# Alimentatore_LM317.net
KiCad netlist of a schematic drawn in EAGLE
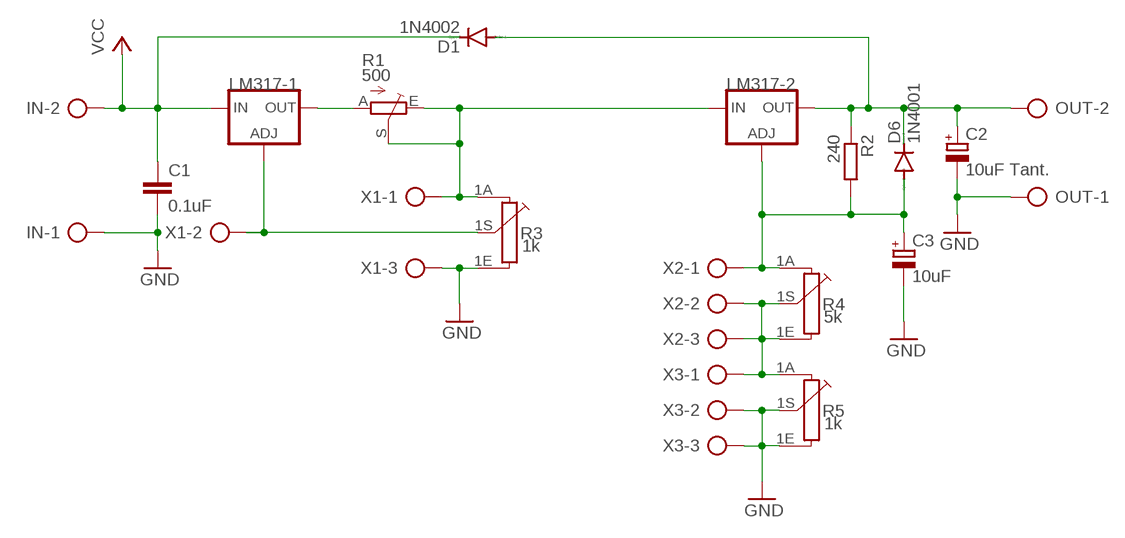
[diagram p0: schematic, sheet 1]

(export (version "E")
  (design (tool "Eeschema 10.0.6"))
  (components
    (comp (ref "C1")
      (value "0.1uF")
      (footprint "eagle-import:C025-024X044")
      (libsource (lib "eagle-import") (part "C-EU025-024X044"))
    )
    (comp (ref "C2")
      (value "10uF Tant.")
      (footprint "eagle-import:E2-5")
      (libsource (lib "eagle-import") (part "CPOL-EUE2-5"))
    )
    (comp (ref "C3")
      (value "10uF")
      (footprint "eagle-import:E2-5")
      (libsource (lib "eagle-import") (part "CPOL-EUE2-5"))
    )
    (comp (ref "D1")
      (value "1N4002")
      (footprint "eagle-import:DIOAD860W70L460D235B")
      (libsource (lib "eagle-import") (part "1N4004DO-41"))
    )
    (comp (ref "D6")
      (value "1N4001")
      (footprint "eagle-import:DIOAD860W70L460D235B")
      (libsource (lib "eagle-import") (part "1N4004DO-41"))
    )
    (comp (ref "IN")
      (value "SMKDSP_1,5/2")
      (footprint "eagle-import:SMKDSP_1,5_2")
      (fields (field (name "MF") "FARNELL") (field (name "MPN") "1733570"))
      (libsource (lib "eagle-import") (part "SMKDSP_1,5/2"))
    )
    (comp (ref "LM317-1")
      (value "LM317TS317TS_TO220")
      (footprint "eagle-import:TO220V")
      (libsource (lib "eagle-import") (part "LM317TS317TS_TO220"))
    )
    (comp (ref "LM317-2")
      (value "LM317TS317TS_TO220")
      (footprint "eagle-import:TO220V")
      (libsource (lib "eagle-import") (part "LM317TS317TS_TO220"))
    )
    (comp (ref "OUT")
      (value "SMKDSP_1,5/2")
      (footprint "eagle-import:SMKDSP_1,5_2")
      (fields (field (name "MF") "FARNELL") (field (name "MPN") "1733570"))
      (libsource (lib "eagle-import") (part "SMKDSP_1,5/2"))
    )
    (comp (ref "R1")
      (value "500")
      (footprint "eagle-import:CA6V")
      (libsource (lib "eagle-import") (part "TRIM_EU-CA6V"))
    )
    (comp (ref "R2")
      (value "240")
      (footprint "eagle-import:0204_7")
      (libsource (lib "eagle-import") (part "R-EU_0204/7"))
    )
    (comp (ref "R3")
      (value "1k")
      (footprint "eagle-import:PC16S")
      (libsource (lib "eagle-import") (part "PC16S"))
    )
    (comp (ref "R4")
      (value "5k")
      (footprint "eagle-import:PC16S")
      (libsource (lib "eagle-import") (part "PC16S"))
    )
    (comp (ref "R5")
      (value "1k")
      (footprint "eagle-import:PC16S")
      (libsource (lib "eagle-import") (part "PC16S"))
    )
    (comp (ref "X1")
      (value "SMKDSP_1,5/3")
      (footprint "eagle-import:SMKDSP_1,5_3")
      (fields (field (name "MF") "FARNELL") (field (name "MPN") "1733583"))
      (libsource (lib "eagle-import") (part "SMKDSP_1,5/3"))
    )
    (comp (ref "X2")
      (value "SMKDSP_1,5/3")
      (footprint "eagle-import:SMKDSP_1,5_3")
      (fields (field (name "MF") "FARNELL") (field (name "MPN") "1733583"))
      (libsource (lib "eagle-import") (part "SMKDSP_1,5/3"))
    )
    (comp (ref "X3")
      (value "SMKDSP_1,5/3")
      (footprint "eagle-import:SMKDSP_1,5_3")
      (fields (field (name "MF") "FARNELL") (field (name "MPN") "1733583"))
      (libsource (lib "eagle-import") (part "SMKDSP_1,5/3"))
    )
  )
  (nets
    (net (code "1") (name "GND") (class "Default")
      (node (ref "C1") (pin "2") (pinfunction "2_2") (pintype "passive"))
      (node (ref "C2") (pin "-") (pinfunction "-_-") (pintype "passive"))
      (node (ref "C3") (pin "-") (pinfunction "-_-") (pintype "passive"))
      (node (ref "IN") (pin "1") (pinfunction "KL_1") (pintype "passive"))
      (node (ref "OUT") (pin "1") (pinfunction "KL_1") (pintype "passive"))
      (node (ref "R3") (pin "1E") (pinfunction "1E_1E") (pintype "passive"))
      (node (ref "R5") (pin "1E") (pinfunction "1E_1E") (pintype "passive"))
      (node (ref "R5") (pin "1S") (pinfunction "1S_1S") (pintype "passive"))
      (node (ref "X1") (pin "3") (pinfunction "KL_3") (pintype "passive"))
      (node (ref "X3") (pin "2") (pinfunction "KL_2") (pintype "passive"))
      (node (ref "X3") (pin "3") (pinfunction "KL_3") (pintype "passive"))
    )
    (net (code "2") (name "Net-(D1-A)") (class "Default")
      (node (ref "C2") (pin "+") (pinfunction "+_+") (pintype "passive"))
      (node (ref "D1") (pin "2") (pinfunction "A_2") (pintype "passive"))
      (node (ref "D6") (pin "1") (pinfunction "C_1") (pintype "passive"))
      (node (ref "LM317-2") (pin "2") (pinfunction "OUT_2") (pintype "passive"))
      (node (ref "OUT") (pin "2") (pinfunction "KL_2") (pintype "passive"))
      (node (ref "R2") (pin "1") (pinfunction "1_1") (pintype "passive"))
    )
    (net (code "3") (name "Net-(D6-A)") (class "Default")
      (node (ref "C3") (pin "+") (pinfunction "+_+") (pintype "passive"))
      (node (ref "D6") (pin "2") (pinfunction "A_2") (pintype "passive"))
      (node (ref "LM317-2") (pin "1") (pinfunction "ADJ_1") (pintype "input"))
      (node (ref "R2") (pin "2") (pinfunction "2_2") (pintype "passive"))
      (node (ref "R4") (pin "1A") (pinfunction "1A_1A") (pintype "passive"))
      (node (ref "X2") (pin "1") (pinfunction "KL_1") (pintype "passive"))
    )
    (net (code "4") (name "Net-(LM317-1-ADJ)") (class "Default")
      (node (ref "LM317-1") (pin "1") (pinfunction "ADJ_1") (pintype "input"))
      (node (ref "R3") (pin "1S") (pinfunction "1S_1S") (pintype "passive"))
      (node (ref "X1") (pin "2") (pinfunction "KL_2") (pintype "passive"))
    )
    (net (code "5") (name "Net-(LM317-1-OUT)") (class "Default")
      (node (ref "LM317-1") (pin "2") (pinfunction "OUT_2") (pintype "passive"))
      (node (ref "R1") (pin "A") (pinfunction "A_A") (pintype "passive"))
    )
    (net (code "6") (name "Net-(LM317-2-IN)") (class "Default")
      (node (ref "LM317-2") (pin "3") (pinfunction "IN_3") (pintype "input"))
      (node (ref "R1") (pin "E") (pinfunction "E_E") (pintype "passive"))
      (node (ref "R1") (pin "S") (pinfunction "S_S") (pintype "passive"))
      (node (ref "R3") (pin "1A") (pinfunction "1A_1A") (pintype "passive"))
      (node (ref "X1") (pin "1") (pinfunction "KL_1") (pintype "passive"))
    )
    (net (code "7") (name "Net-(X2B-KL)") (class "Default")
      (node (ref "R4") (pin "1E") (pinfunction "1E_1E") (pintype "passive"))
      (node (ref "R4") (pin "1S") (pinfunction "1S_1S") (pintype "passive"))
      (node (ref "R5") (pin "1A") (pinfunction "1A_1A") (pintype "passive"))
      (node (ref "X2") (pin "2") (pinfunction "KL_2") (pintype "passive"))
      (node (ref "X2") (pin "3") (pinfunction "KL_3") (pintype "passive"))
      (node (ref "X3") (pin "1") (pinfunction "KL_1") (pintype "passive"))
    )
    (net (code "8") (name "VCC") (class "Default")
      (node (ref "C1") (pin "1") (pinfunction "1_1") (pintype "passive"))
      (node (ref "D1") (pin "1") (pinfunction "C_1") (pintype "passive"))
      (node (ref "IN") (pin "2") (pinfunction "KL_2") (pintype "passive"))
      (node (ref "LM317-1") (pin "3") (pinfunction "IN_3") (pintype "input"))
    )
  )
)
